# MyShield_FTDI_ESP_v20_kropp.net
KiCad netlist of a schematic drawn in EAGLE
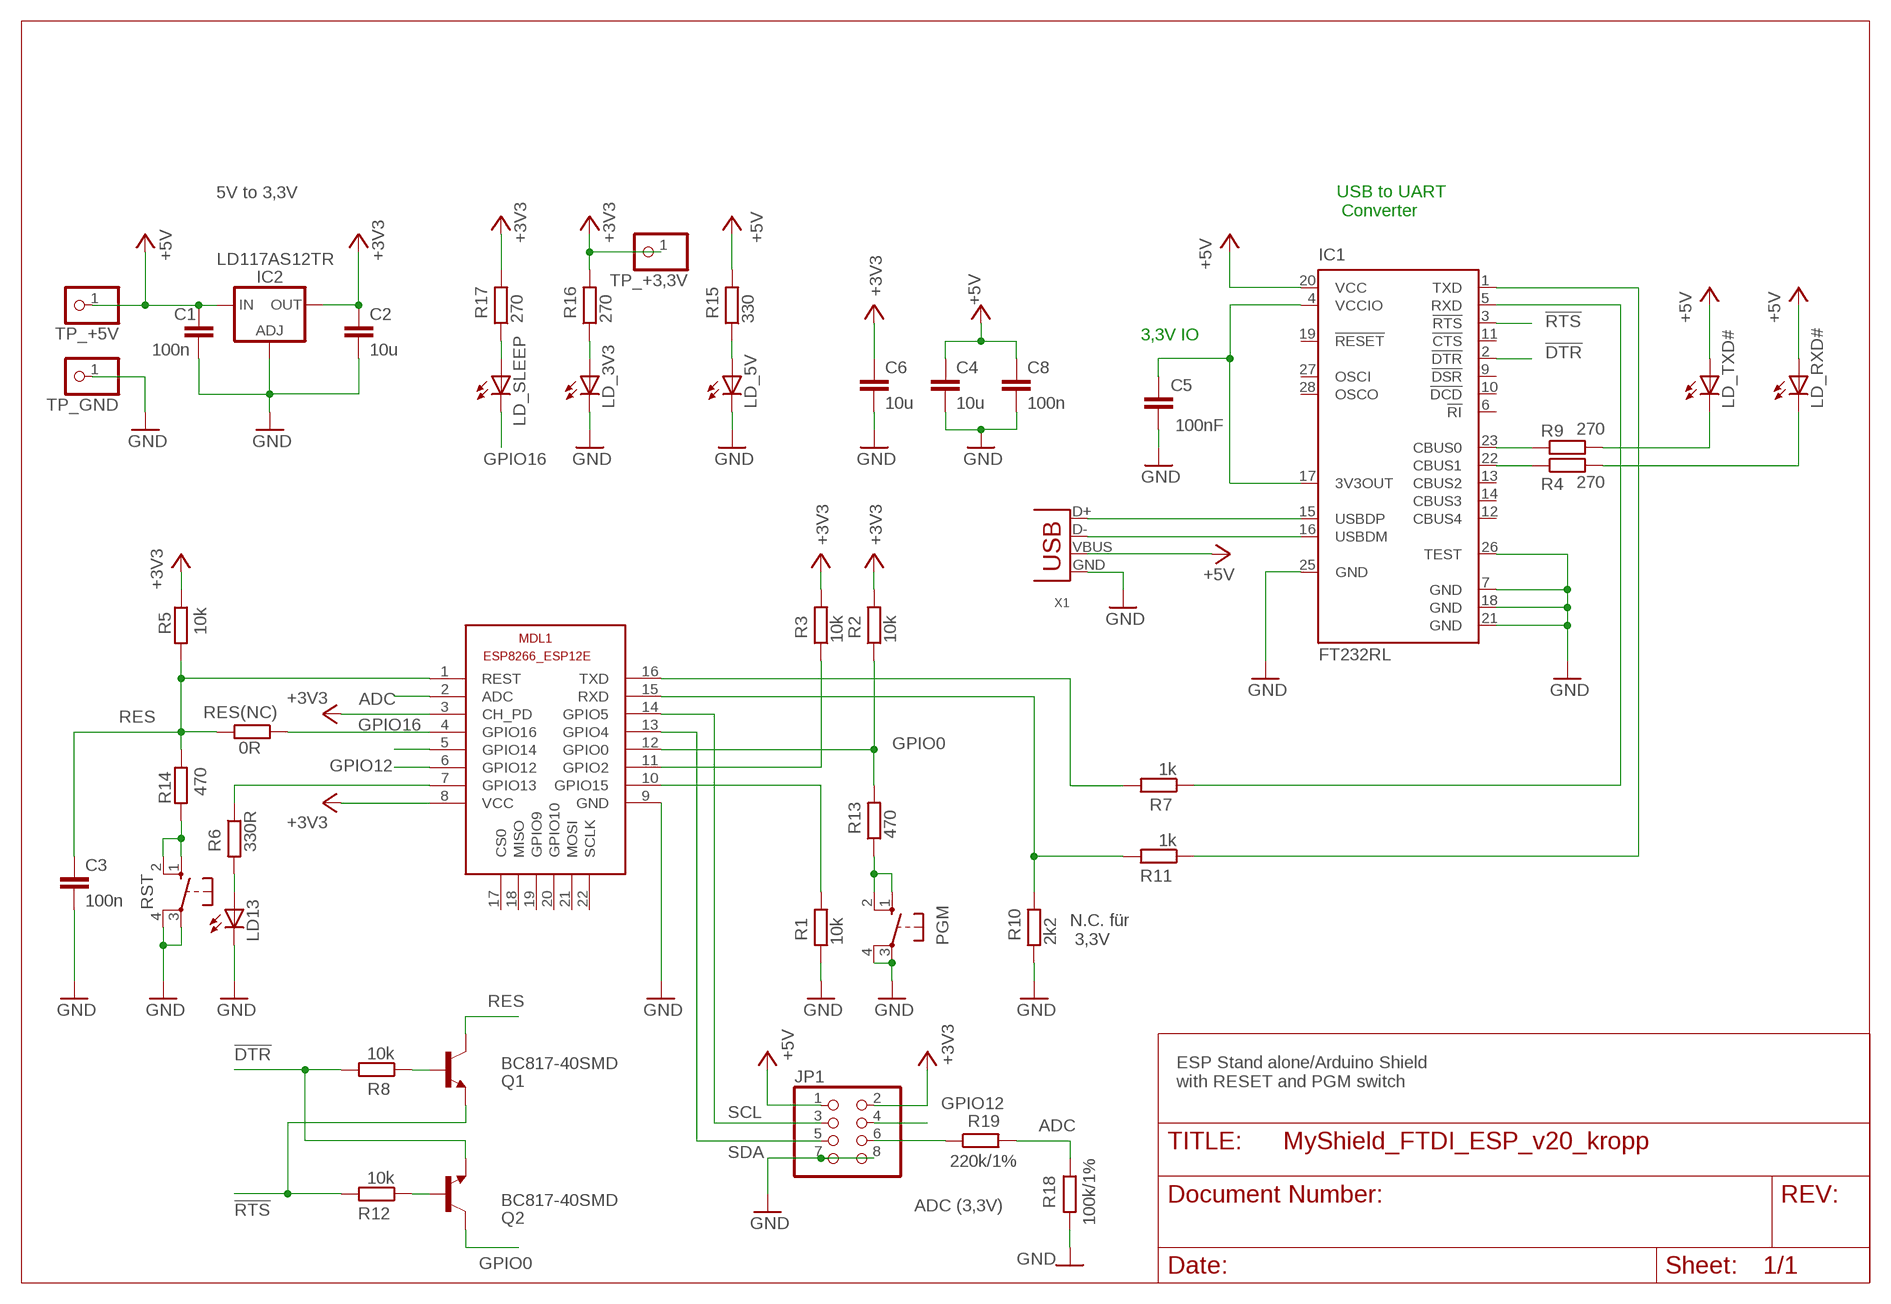
[diagram p0: schematic, sheet 1]

(export (version "E")
  (design (tool "Eeschema 10.0.6"))
  (components
    (comp (ref "C1")
      (value "100n")
      (footprint "eagle-import:C1206")
      (libsource (lib "eagle-import") (part "C-EUC1206"))
    )
    (comp (ref "C2")
      (value "10u")
      (footprint "eagle-import:C1206")
      (libsource (lib "eagle-import") (part "C-EUC1206"))
    )
    (comp (ref "C3")
      (value "100n")
      (footprint "eagle-import:C1206")
      (libsource (lib "eagle-import") (part "C-EUC1206"))
    )
    (comp (ref "C4")
      (value "10u")
      (footprint "eagle-import:C1206")
      (libsource (lib "eagle-import") (part "C-EUC1206"))
    )
    (comp (ref "C5")
      (value "100nF")
      (footprint "eagle-import:C1206")
      (libsource (lib "eagle-import") (part "resistor_C-EUC1206"))
    )
    (comp (ref "C6")
      (value "10u")
      (footprint "eagle-import:C1206")
      (libsource (lib "eagle-import") (part "C-EUC1206"))
    )
    (comp (ref "C8")
      (value "100n")
      (footprint "eagle-import:C1206")
      (libsource (lib "eagle-import") (part "resistor_C-EUC1206"))
    )
    (comp (ref "IC1")
      (value "FT232RL")
      (footprint "eagle-import:SSOP28")
      (libsource (lib "eagle-import") (part "FT232RL"))
    )
    (comp (ref "IC2")
      (value "LD117AS12TR")
      (footprint "eagle-import:SOT223")
      (libsource (lib "eagle-import") (part "LD117A?S12TR"))
    )
    (comp (ref "JP1")
      (value "PINHD-2X4")
      (footprint "eagle-import:2X04")
      (libsource (lib "eagle-import") (part "PINHD-2X4"))
    )
    (comp (ref "LD13")
      (value "LEDSMT1206")
      (footprint "eagle-import:1206")
      (libsource (lib "eagle-import") (part "LEDSMT1206"))
    )
    (comp (ref "LD_3V3")
      (value "LEDSMT1206")
      (footprint "eagle-import:1206")
      (libsource (lib "eagle-import") (part "LEDSMT1206"))
    )
    (comp (ref "LD_5V")
      (value "LEDSMT1206")
      (footprint "eagle-import:1206")
      (libsource (lib "eagle-import") (part "LEDSMT1206"))
    )
    (comp (ref "LD_RXD#")
      (value "LEDSMT1206")
      (footprint "eagle-import:1206")
      (libsource (lib "eagle-import") (part "LEDSMT1206"))
    )
    (comp (ref "LD_SLEEP")
      (value "LEDSMT1206")
      (footprint "eagle-import:1206")
      (libsource (lib "eagle-import") (part "LEDSMT1206"))
    )
    (comp (ref "LD_TXD#")
      (value "LEDSMT1206")
      (footprint "eagle-import:1206")
      (libsource (lib "eagle-import") (part "LEDSMT1206"))
    )
    (comp (ref "MDL1")
      (value "ESP8266-12EESP8266-ESP12E")
      (footprint "eagle-import:ESP8266-ESP12E")
      (libsource (lib "eagle-import") (part "ESP8266-12EESP8266-ESP12E"))
    )
    (comp (ref "PGM")
      (value "10-XX")
      (footprint "eagle-import:B3F-10XX")
      (fields (field (name "MPN") "B3F-1000"))
      (libsource (lib "eagle-import") (part "10-XX"))
    )
    (comp (ref "Q1")
      (value "BC817-40SMD")
      (footprint "eagle-import:SOT23-BEC")
      (libsource (lib "eagle-import") (part "BC817SMD-40"))
    )
    (comp (ref "Q2")
      (value "BC817-40SMD")
      (footprint "eagle-import:SOT23-BEC")
      (libsource (lib "eagle-import") (part "BC817SMD-40"))
    )
    (comp (ref "R1")
      (value "10k")
      (footprint "eagle-import:R1206")
      (libsource (lib "eagle-import") (part "R-EU_R1206"))
    )
    (comp (ref "R2")
      (value "10k")
      (footprint "eagle-import:R1206")
      (libsource (lib "eagle-import") (part "R-EU_R1206"))
    )
    (comp (ref "R3")
      (value "10k")
      (footprint "eagle-import:R1206")
      (libsource (lib "eagle-import") (part "R-EU_R1206"))
    )
    (comp (ref "R4")
      (value "270")
      (footprint "eagle-import:R1206")
      (libsource (lib "eagle-import") (part "resistor_R-EU_R1206"))
    )
    (comp (ref "R5")
      (value "10k")
      (footprint "eagle-import:R1206")
      (libsource (lib "eagle-import") (part "R-EU_R1206"))
    )
    (comp (ref "R6")
      (value "330R")
      (footprint "eagle-import:R1206")
      (libsource (lib "eagle-import") (part "R-EU_R1206"))
    )
    (comp (ref "R7")
      (value "1k")
      (footprint "eagle-import:R1206")
      (libsource (lib "eagle-import") (part "R-EU_R1206"))
    )
    (comp (ref "R8")
      (value "10k")
      (footprint "eagle-import:R1206")
      (libsource (lib "eagle-import") (part "R-EU_R1206"))
    )
    (comp (ref "R9")
      (value "270")
      (footprint "eagle-import:R1206")
      (libsource (lib "eagle-import") (part "resistor_R-EU_R1206"))
    )
    (comp (ref "R10")
      (value "2k2")
      (footprint "eagle-import:R1206")
      (libsource (lib "eagle-import") (part "R-EU_R1206"))
    )
    (comp (ref "R11")
      (value "1k")
      (footprint "eagle-import:R1206")
      (libsource (lib "eagle-import") (part "R-EU_R1206"))
    )
    (comp (ref "R12")
      (value "10k")
      (footprint "eagle-import:R1206")
      (libsource (lib "eagle-import") (part "R-EU_R1206"))
    )
    (comp (ref "R13")
      (value "470")
      (footprint "eagle-import:R1206")
      (libsource (lib "eagle-import") (part "R-EU_R1206"))
    )
    (comp (ref "R14")
      (value "470")
      (footprint "eagle-import:R1206")
      (libsource (lib "eagle-import") (part "R-EU_R1206"))
    )
    (comp (ref "R15")
      (value "330")
      (footprint "eagle-import:R1206")
      (libsource (lib "eagle-import") (part "R-EU_R1206"))
    )
    (comp (ref "R16")
      (value "270")
      (footprint "eagle-import:R1206")
      (libsource (lib "eagle-import") (part "R-EU_R1206"))
    )
    (comp (ref "R17")
      (value "270")
      (footprint "eagle-import:R1206")
      (libsource (lib "eagle-import") (part "R-EU_R1206"))
    )
    (comp (ref "R18")
      (value "100k/1%")
      (footprint "eagle-import:R1206")
      (libsource (lib "eagle-import") (part "R-EU_R1206"))
    )
    (comp (ref "R19")
      (value "220k/1%")
      (footprint "eagle-import:R1206")
      (libsource (lib "eagle-import") (part "R-EU_R1206"))
    )
    (comp (ref "RES(NC)")
      (value "0R")
      (footprint "eagle-import:R0805")
      (libsource (lib "eagle-import") (part "R-EU_R0805"))
    )
    (comp (ref "RST")
      (value "10-XX")
      (footprint "eagle-import:B3F-10XX")
      (fields (field (name "MPN") "B3F-1000"))
      (libsource (lib "eagle-import") (part "10-XX"))
    )
    (comp (ref "TP_+3,3V")
      (value "PINHD-1X1")
      (footprint "eagle-import:1X01")
      (libsource (lib "eagle-import") (part "PINHD-1X1"))
    )
    (comp (ref "TP_+5V")
      (value "PINHD-1X1")
      (footprint "eagle-import:1X01")
      (libsource (lib "eagle-import") (part "PINHD-1X1"))
    )
    (comp (ref "TP_GND")
      (value "PINHD-1X1")
      (footprint "eagle-import:1X01")
      (libsource (lib "eagle-import") (part "PINHD-1X1"))
    )
    (comp (ref "X1")
      (value "USB-A-S")
      (footprint "eagle-import:USB-A-S")
      (libsource (lib "eagle-import") (part "USB-A-S"))
    )
  )
  (nets
    (net (code "1") (name "+3V3") (class "Default")
      (node (ref "C2") (pin "1") (pinfunction "1_1") (pintype "passive"))
      (node (ref "C6") (pin "1") (pinfunction "1_1") (pintype "passive"))
      (node (ref "IC2") (pin "4") (pinfunction "OUT_4") (pintype "passive"))
      (node (ref "JP1") (pin "2") (pinfunction "2_2") (pintype "passive"))
      (node (ref "MDL1") (pin "3") (pinfunction "CH_PD_3") (pintype "bidirectional"))
      (node (ref "MDL1") (pin "8") (pinfunction "VCC_8") (pintype "bidirectional"))
      (node (ref "R16") (pin "2") (pinfunction "2_2") (pintype "passive"))
      (node (ref "R17") (pin "2") (pinfunction "2_2") (pintype "passive"))
      (node (ref "R2") (pin "2") (pinfunction "2_2") (pintype "passive"))
      (node (ref "R3") (pin "2") (pinfunction "2_2") (pintype "passive"))
      (node (ref "R5") (pin "1") (pinfunction "1_1") (pintype "passive"))
      (node (ref "TP_+3,3V") (pin "1") (pinfunction "1_1") (pintype "passive"))
    )
    (net (code "2") (name "+5V") (class "Default")
      (node (ref "C1") (pin "1") (pinfunction "1_1") (pintype "passive"))
      (node (ref "C4") (pin "1") (pinfunction "1_1") (pintype "passive"))
      (node (ref "C8") (pin "1") (pinfunction "1_1") (pintype "passive"))
      (node (ref "IC1") (pin "20") (pinfunction "VCC_20") (pintype "power_in"))
      (node (ref "IC2") (pin "3") (pinfunction "IN_3") (pintype "input"))
      (node (ref "JP1") (pin "1") (pinfunction "1_1") (pintype "passive"))
      (node (ref "LD_RXD#") (pin "A") (pinfunction "A_A") (pintype "passive"))
      (node (ref "LD_TXD#") (pin "A") (pinfunction "A_A") (pintype "passive"))
      (node (ref "R15") (pin "2") (pinfunction "2_2") (pintype "passive"))
      (node (ref "TP_+5V") (pin "1") (pinfunction "1_1") (pintype "passive"))
      (node (ref "X1") (pin "VBUS") (pinfunction "VBUS_VBUS") (pintype "bidirectional"))
    )
    (net (code "3") (name "/ADC") (class "Default")
      (node (ref "MDL1") (pin "2") (pinfunction "ADC_2") (pintype "bidirectional"))
      (node (ref "R18") (pin "1") (pinfunction "1_1") (pintype "passive"))
      (node (ref "R19") (pin "2") (pinfunction "2_2") (pintype "passive"))
    )
    (net (code "4") (name "/GPIO0") (class "Default")
      (node (ref "MDL1") (pin "12") (pinfunction "GPIO0_12") (pintype "bidirectional"))
      (node (ref "Q2") (pin "C") (pinfunction "C_C") (pintype "passive"))
      (node (ref "R13") (pin "2") (pinfunction "2_2") (pintype "passive"))
      (node (ref "R2") (pin "1") (pinfunction "1_1") (pintype "passive"))
    )
    (net (code "5") (name "/GPIO12") (class "Default")
      (node (ref "JP1") (pin "4") (pinfunction "4_4") (pintype "passive"))
      (node (ref "MDL1") (pin "6") (pinfunction "GPIO12_6") (pintype "bidirectional"))
    )
    (net (code "6") (name "/GPIO16") (class "Default")
      (node (ref "LD_SLEEP") (pin "C") (pinfunction "C_C") (pintype "passive"))
      (node (ref "MDL1") (pin "4") (pinfunction "GPIO16_4") (pintype "bidirectional"))
      (node (ref "RES(NC)") (pin "1") (pinfunction "1_1") (pintype "passive"))
    )
    (net (code "7") (name "/RES") (class "Default")
      (node (ref "C3") (pin "1") (pinfunction "1_1") (pintype "passive"))
      (node (ref "MDL1") (pin "1") (pinfunction "REST_1") (pintype "bidirectional"))
      (node (ref "Q1") (pin "C") (pinfunction "C_C") (pintype "passive"))
      (node (ref "R14") (pin "1") (pinfunction "1_1") (pintype "passive"))
      (node (ref "R5") (pin "2") (pinfunction "2_2") (pintype "passive"))
      (node (ref "RES(NC)") (pin "2") (pinfunction "2_2") (pintype "passive"))
    )
    (net (code "8") (name "/SCL") (class "Default")
      (node (ref "JP1") (pin "3") (pinfunction "3_3") (pintype "passive"))
      (node (ref "MDL1") (pin "14") (pinfunction "GPIO5_14") (pintype "bidirectional"))
    )
    (net (code "9") (name "/SDA") (class "Default")
      (node (ref "JP1") (pin "5") (pinfunction "5_5") (pintype "passive"))
      (node (ref "MDL1") (pin "13") (pinfunction "GPIO4_13") (pintype "bidirectional"))
    )
    (net (code "10") (name "/~{DTR}") (class "Default")
      (node (ref "IC1") (pin "2") (pinfunction "~{DTR}_2") (pintype "output"))
      (node (ref "Q2") (pin "E") (pinfunction "E_E") (pintype "passive"))
      (node (ref "R8") (pin "2") (pinfunction "2_2") (pintype "passive"))
    )
    (net (code "11") (name "/~{RTS}") (class "Default")
      (node (ref "IC1") (pin "3") (pinfunction "~{RTS}_3") (pintype "output"))
      (node (ref "Q1") (pin "E") (pinfunction "E_E") (pintype "passive"))
      (node (ref "R12") (pin "2") (pinfunction "2_2") (pintype "passive"))
    )
    (net (code "12") (name "GND") (class "Default")
      (node (ref "C1") (pin "2") (pinfunction "2_2") (pintype "passive"))
      (node (ref "C2") (pin "2") (pinfunction "2_2") (pintype "passive"))
      (node (ref "C3") (pin "2") (pinfunction "2_2") (pintype "passive"))
      (node (ref "C4") (pin "2") (pinfunction "2_2") (pintype "passive"))
      (node (ref "C5") (pin "1") (pinfunction "1_1") (pintype "passive"))
      (node (ref "C6") (pin "2") (pinfunction "2_2") (pintype "passive"))
      (node (ref "C8") (pin "2") (pinfunction "2_2") (pintype "passive"))
      (node (ref "IC1") (pin "18") (pinfunction "GND_18") (pintype "power_in"))
      (node (ref "IC1") (pin "21") (pinfunction "GND_21") (pintype "power_in"))
      (node (ref "IC1") (pin "25") (pinfunction "GND_25") (pintype "power_in"))
      (node (ref "IC1") (pin "26") (pinfunction "TEST_26") (pintype "input"))
      (node (ref "IC1") (pin "7") (pinfunction "GND_7") (pintype "power_in"))
      (node (ref "IC2") (pin "1") (pinfunction "ADJ_1") (pintype "input"))
      (node (ref "JP1") (pin "7") (pinfunction "7_7") (pintype "passive"))
      (node (ref "JP1") (pin "8") (pinfunction "8_8") (pintype "passive"))
      (node (ref "LD13") (pin "C") (pinfunction "C_C") (pintype "passive"))
      (node (ref "LD_3V3") (pin "C") (pinfunction "C_C") (pintype "passive"))
      (node (ref "LD_5V") (pin "C") (pinfunction "C_C") (pintype "passive"))
      (node (ref "MDL1") (pin "9") (pinfunction "GND_9") (pintype "bidirectional"))
      (node (ref "PGM") (pin "3") (pinfunction "P_3") (pintype "passive"))
      (node (ref "PGM") (pin "4") (pinfunction "P1_4") (pintype "passive"))
      (node (ref "R1") (pin "1") (pinfunction "1_1") (pintype "passive"))
      (node (ref "R10") (pin "1") (pinfunction "1_1") (pintype "passive"))
      (node (ref "R18") (pin "2") (pinfunction "2_2") (pintype "passive"))
      (node (ref "RST") (pin "3") (pinfunction "P_3") (pintype "passive"))
      (node (ref "RST") (pin "4") (pinfunction "P1_4") (pintype "passive"))
      (node (ref "TP_GND") (pin "1") (pinfunction "1_1") (pintype "passive"))
      (node (ref "X1") (pin "GND") (pinfunction "GND_GND") (pintype "bidirectional"))
    )
    (net (code "13") (name "Net-(IC1-3V3OUT)") (class "Default")
      (node (ref "C5") (pin "2") (pinfunction "2_2") (pintype "passive"))
      (node (ref "IC1") (pin "17") (pinfunction "3V3OUT_17") (pintype "output"))
      (node (ref "IC1") (pin "4") (pinfunction "VCCIO_4") (pintype "power_in"))
    )
    (net (code "14") (name "Net-(IC1-CBUS0)") (class "Default")
      (node (ref "IC1") (pin "23") (pinfunction "CBUS0_23") (pintype "bidirectional"))
      (node (ref "R9") (pin "1") (pinfunction "1_1") (pintype "passive"))
    )
    (net (code "15") (name "Net-(IC1-CBUS1)") (class "Default")
      (node (ref "IC1") (pin "22") (pinfunction "CBUS1_22") (pintype "bidirectional"))
      (node (ref "R4") (pin "1") (pinfunction "1_1") (pintype "passive"))
    )
    (net (code "16") (name "Net-(IC1-RXD)") (class "Default")
      (node (ref "IC1") (pin "5") (pinfunction "RXD_5") (pintype "input"))
      (node (ref "R7") (pin "1") (pinfunction "1_1") (pintype "passive"))
    )
    (net (code "17") (name "Net-(IC1-TXD)") (class "Default")
      (node (ref "IC1") (pin "1") (pinfunction "TXD_1") (pintype "output"))
      (node (ref "R11") (pin "1") (pinfunction "1_1") (pintype "passive"))
    )
    (net (code "18") (name "Net-(IC1-USBDM)") (class "Default")
      (node (ref "IC1") (pin "16") (pinfunction "USBDM_16") (pintype "bidirectional"))
      (node (ref "X1") (pin "D-") (pinfunction "D-_D-") (pintype "bidirectional"))
    )
    (net (code "19") (name "Net-(IC1-USBDP)") (class "Default")
      (node (ref "IC1") (pin "15") (pinfunction "USBDP_15") (pintype "bidirectional"))
      (node (ref "X1") (pin "D+") (pinfunction "D+_D+") (pintype "bidirectional"))
    )
    (net (code "20") (name "Net-(JP1-Pad6)") (class "Default")
      (node (ref "JP1") (pin "6") (pinfunction "6_6") (pintype "passive"))
      (node (ref "R19") (pin "1") (pinfunction "1_1") (pintype "passive"))
    )
    (net (code "21") (name "Net-(LD13-PadA)") (class "Default")
      (node (ref "LD13") (pin "A") (pinfunction "A_A") (pintype "passive"))
      (node (ref "R6") (pin "2") (pinfunction "2_2") (pintype "passive"))
    )
    (net (code "22") (name "Net-(LD_3V3-PadA)") (class "Default")
      (node (ref "LD_3V3") (pin "A") (pinfunction "A_A") (pintype "passive"))
      (node (ref "R16") (pin "1") (pinfunction "1_1") (pintype "passive"))
    )
    (net (code "23") (name "Net-(LD_5V-PadA)") (class "Default")
      (node (ref "LD_5V") (pin "A") (pinfunction "A_A") (pintype "passive"))
      (node (ref "R15") (pin "1") (pinfunction "1_1") (pintype "passive"))
    )
    (net (code "24") (name "Net-(LD_RXD#-PadC)") (class "Default")
      (node (ref "LD_RXD#") (pin "C") (pinfunction "C_C") (pintype "passive"))
      (node (ref "R4") (pin "2") (pinfunction "2_2") (pintype "passive"))
    )
    (net (code "25") (name "Net-(LD_SLEEP-PadA)") (class "Default")
      (node (ref "LD_SLEEP") (pin "A") (pinfunction "A_A") (pintype "passive"))
      (node (ref "R17") (pin "1") (pinfunction "1_1") (pintype "passive"))
    )
    (net (code "26") (name "Net-(LD_TXD#-PadC)") (class "Default")
      (node (ref "LD_TXD#") (pin "C") (pinfunction "C_C") (pintype "passive"))
      (node (ref "R9") (pin "2") (pinfunction "2_2") (pintype "passive"))
    )
    (net (code "27") (name "Net-(MDL1-GPIO2)") (class "Default")
      (node (ref "MDL1") (pin "11") (pinfunction "GPIO2_11") (pintype "bidirectional"))
      (node (ref "R3") (pin "1") (pinfunction "1_1") (pintype "passive"))
    )
    (net (code "28") (name "Net-(MDL1-GPIO13)") (class "Default")
      (node (ref "MDL1") (pin "7") (pinfunction "GPIO13_7") (pintype "bidirectional"))
      (node (ref "R6") (pin "1") (pinfunction "1_1") (pintype "passive"))
    )
    (net (code "29") (name "Net-(MDL1-GPIO15)") (class "Default")
      (node (ref "MDL1") (pin "10") (pinfunction "GPIO15_10") (pintype "bidirectional"))
      (node (ref "R1") (pin "2") (pinfunction "2_2") (pintype "passive"))
    )
    (net (code "30") (name "Net-(MDL1-RXD)") (class "Default")
      (node (ref "MDL1") (pin "15") (pinfunction "RXD_15") (pintype "bidirectional"))
      (node (ref "R10") (pin "2") (pinfunction "2_2") (pintype "passive"))
      (node (ref "R11") (pin "2") (pinfunction "2_2") (pintype "passive"))
    )
    (net (code "31") (name "Net-(MDL1-TXD)") (class "Default")
      (node (ref "MDL1") (pin "16") (pinfunction "TXD_16") (pintype "bidirectional"))
      (node (ref "R7") (pin "2") (pinfunction "2_2") (pintype "passive"))
    )
    (net (code "32") (name "Net-(PGM-S)") (class "Default")
      (node (ref "PGM") (pin "1") (pinfunction "S_1") (pintype "passive"))
      (node (ref "PGM") (pin "2") (pinfunction "S1_2") (pintype "passive"))
      (node (ref "R13") (pin "1") (pinfunction "1_1") (pintype "passive"))
    )
    (net (code "33") (name "Net-(Q1-PadB)") (class "Default")
      (node (ref "Q1") (pin "B") (pinfunction "B_B") (pintype "passive"))
      (node (ref "R8") (pin "1") (pinfunction "1_1") (pintype "passive"))
    )
    (net (code "34") (name "Net-(Q2-PadB)") (class "Default")
      (node (ref "Q2") (pin "B") (pinfunction "B_B") (pintype "passive"))
      (node (ref "R12") (pin "1") (pinfunction "1_1") (pintype "passive"))
    )
    (net (code "35") (name "Net-(RST-S)") (class "Default")
      (node (ref "R14") (pin "2") (pinfunction "2_2") (pintype "passive"))
      (node (ref "RST") (pin "1") (pinfunction "S_1") (pintype "passive"))
      (node (ref "RST") (pin "2") (pinfunction "S1_2") (pintype "passive"))
    )
    (net (code "36") (name "unconnected-(IC1-CBUS2-Pad13)") (class "Default")
      (node (ref "IC1") (pin "13") (pinfunction "CBUS2_13") (pintype "bidirectional"))
    )
    (net (code "37") (name "unconnected-(IC1-CBUS3-Pad14)") (class "Default")
      (node (ref "IC1") (pin "14") (pinfunction "CBUS3_14") (pintype "bidirectional"))
    )
    (net (code "38") (name "unconnected-(IC1-CBUS4-Pad12)") (class "Default")
      (node (ref "IC1") (pin "12") (pinfunction "CBUS4_12") (pintype "bidirectional"))
    )
    (net (code "39") (name "unconnected-(IC1-OSCI-Pad27)") (class "Default")
      (node (ref "IC1") (pin "27") (pinfunction "OSCI_27") (pintype "input"))
    )
    (net (code "40") (name "unconnected-(IC1-OSCO-Pad28)") (class "Default")
      (node (ref "IC1") (pin "28") (pinfunction "OSCO_28") (pintype "output"))
    )
    (net (code "41") (name "unconnected-(IC1-~{CTS}-Pad11)") (class "Default")
      (node (ref "IC1") (pin "11") (pinfunction "~{CTS}_11") (pintype "input"))
    )
    (net (code "42") (name "unconnected-(IC1-~{DCD}-Pad10)") (class "Default")
      (node (ref "IC1") (pin "10") (pinfunction "~{DCD}_10") (pintype "input"))
    )
    (net (code "43") (name "unconnected-(IC1-~{DSR}-Pad9)") (class "Default")
      (node (ref "IC1") (pin "9") (pinfunction "~{DSR}_9") (pintype "input"))
    )
    (net (code "44") (name "unconnected-(IC1-~{RESET}-Pad19)") (class "Default")
      (node (ref "IC1") (pin "19") (pinfunction "~{RESET}_19") (pintype "input"))
    )
    (net (code "45") (name "unconnected-(IC1-~{RI}-Pad6)") (class "Default")
      (node (ref "IC1") (pin "6") (pinfunction "~{RI}_6") (pintype "input"))
    )
    (net (code "46") (name "unconnected-(MDL1-CS0-Pad17)") (class "Default")
      (node (ref "MDL1") (pin "17") (pinfunction "CS0_17") (pintype "bidirectional"))
    )
    (net (code "47") (name "unconnected-(MDL1-GPIO9-Pad19)") (class "Default")
      (node (ref "MDL1") (pin "19") (pinfunction "GPIO9_19") (pintype "bidirectional"))
    )
    (net (code "48") (name "unconnected-(MDL1-GPIO10-Pad20)") (class "Default")
      (node (ref "MDL1") (pin "20") (pinfunction "GPIO10_20") (pintype "bidirectional"))
    )
    (net (code "49") (name "unconnected-(MDL1-GPIO14-Pad5)") (class "Default")
      (node (ref "MDL1") (pin "5") (pinfunction "GPIO14_5") (pintype "bidirectional"))
    )
    (net (code "50") (name "unconnected-(MDL1-MISO-Pad18)") (class "Default")
      (node (ref "MDL1") (pin "18") (pinfunction "MISO_18") (pintype "bidirectional"))
    )
    (net (code "51") (name "unconnected-(MDL1-MOSI-Pad21)") (class "Default")
      (node (ref "MDL1") (pin "21") (pinfunction "MOSI_21") (pintype "bidirectional"))
    )
    (net (code "52") (name "unconnected-(MDL1-SCLK-Pad22)") (class "Default")
      (node (ref "MDL1") (pin "22") (pinfunction "SCLK_22") (pintype "bidirectional"))
    )
  )
)
